# MystiqueJamma.net
KiCad netlist of a schematic drawn in EAGLE
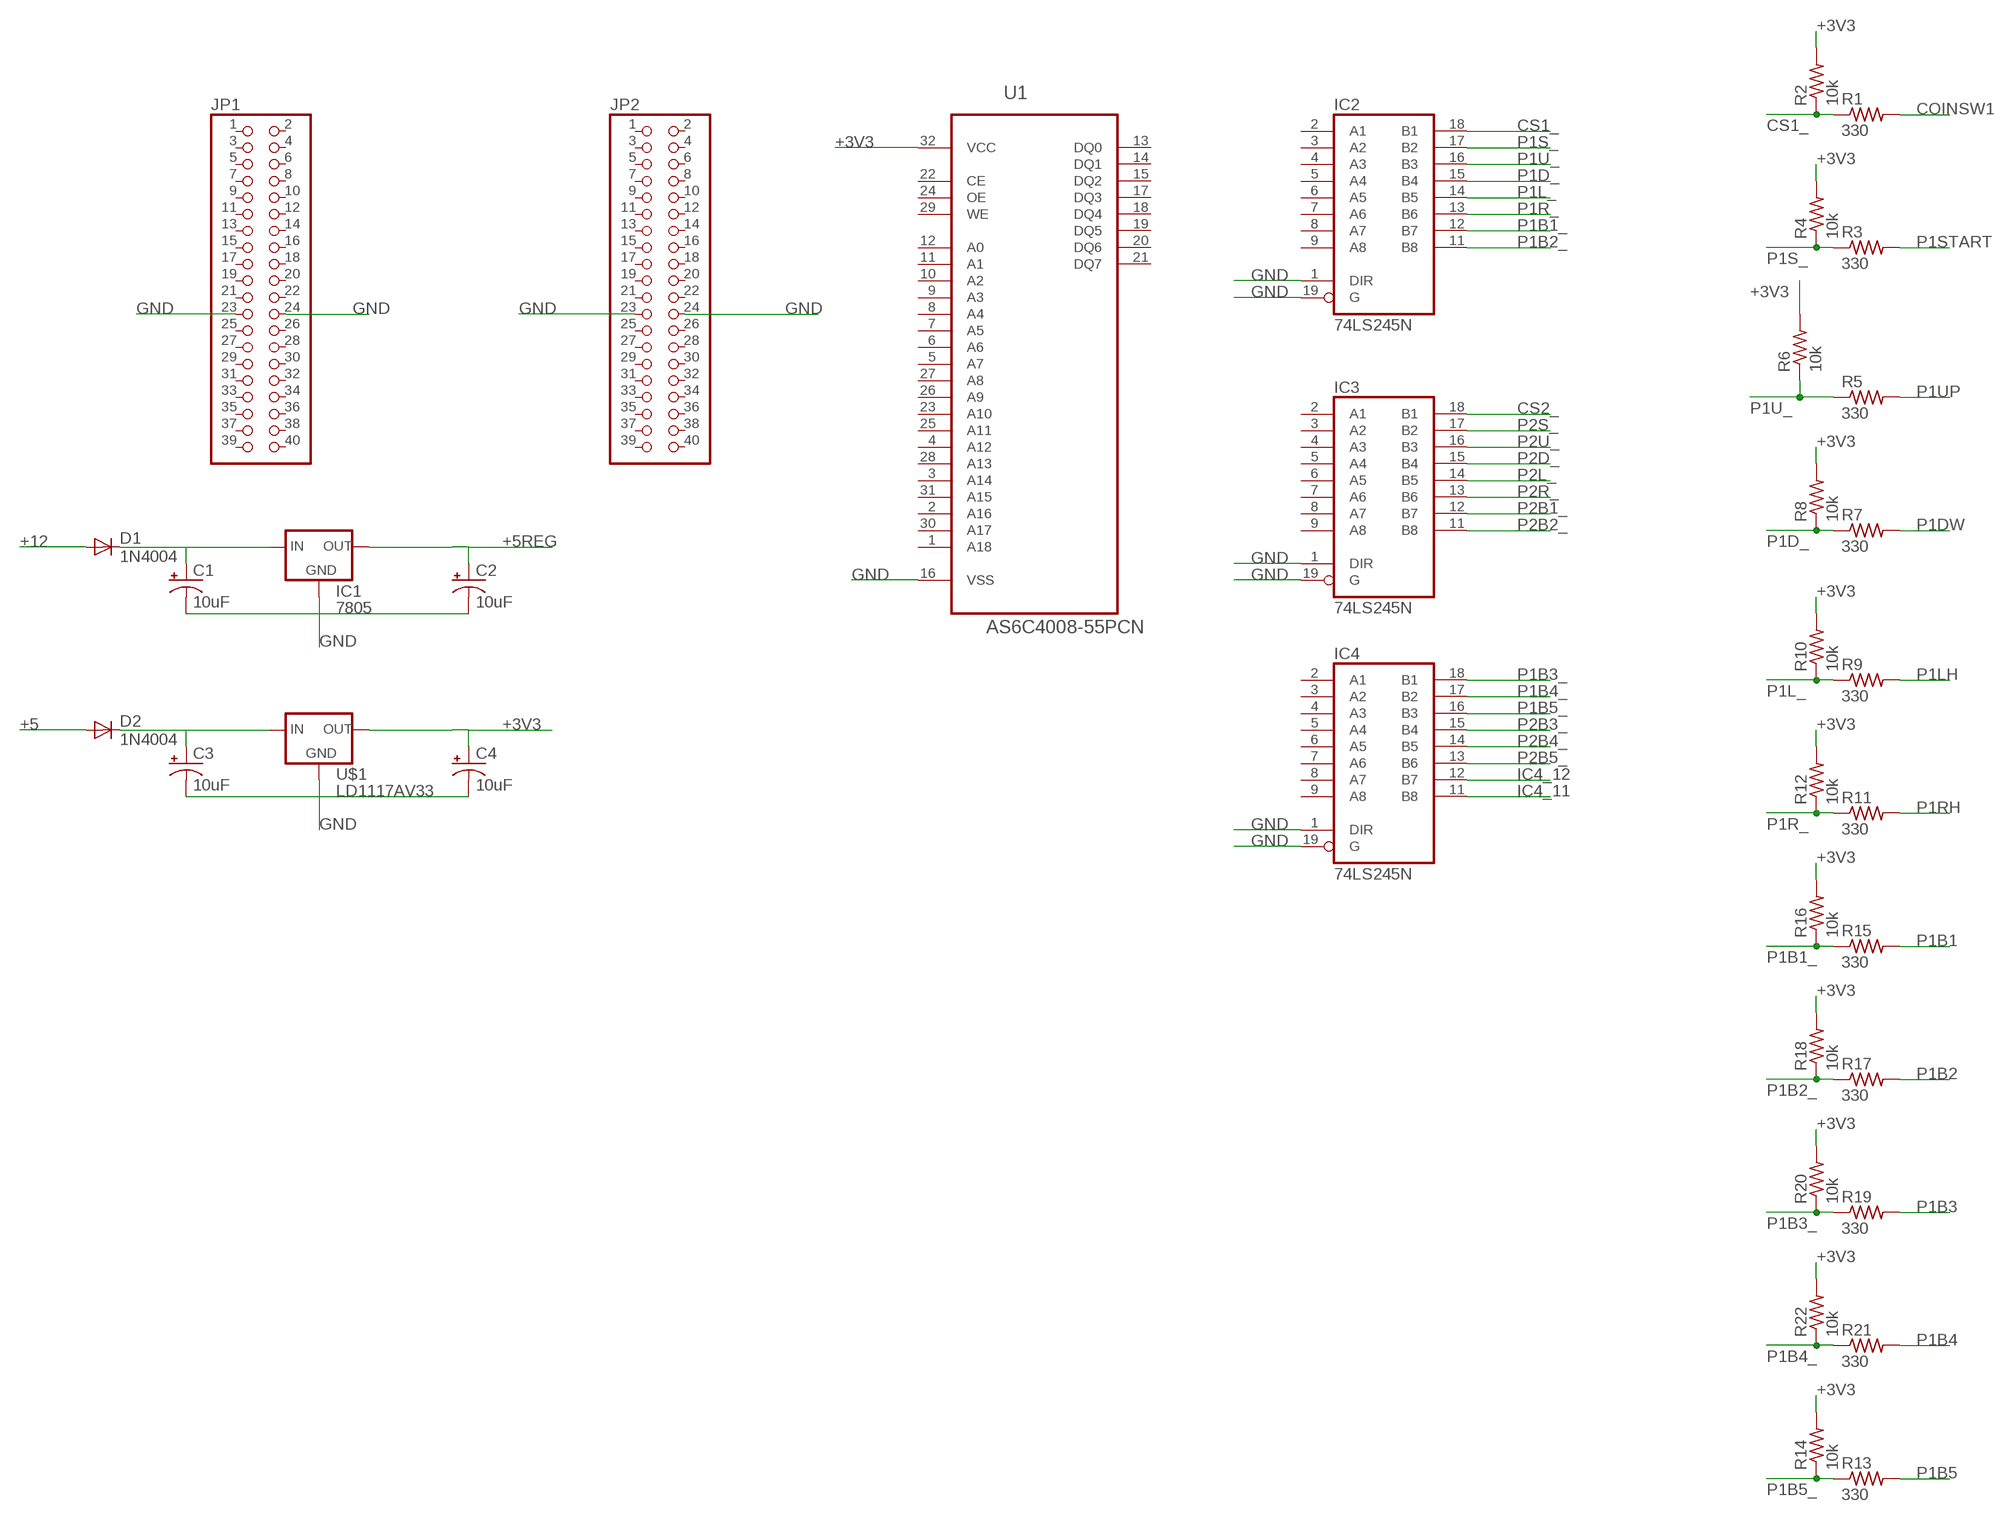
[diagram p0: schematic, sheet 1]

(export (version "E")
  (design (tool "Eeschema 10.0.6"))
  (components
    (comp (ref "C1")
      (value "10uF")
      (footprint "eagle-import:E2,5-5")
      (libsource (lib "eagle-import") (part "CPOL-USE2.5-5"))
    )
    (comp (ref "C2")
      (value "10uF")
      (footprint "eagle-import:E2,5-5")
      (libsource (lib "eagle-import") (part "CPOL-USE2.5-5"))
    )
    (comp (ref "C3")
      (value "10uF")
      (footprint "eagle-import:E2,5-5")
      (libsource (lib "eagle-import") (part "CPOL-USE2.5-5"))
    )
    (comp (ref "C4")
      (value "10uF")
      (footprint "eagle-import:E2,5-5")
      (libsource (lib "eagle-import") (part "CPOL-USE2.5-5"))
    )
    (comp (ref "D1")
      (value "1N4004")
      (footprint "eagle-import:DO41-10")
      (libsource (lib "eagle-import") (part "1N4004"))
    )
    (comp (ref "D2")
      (value "1N4004")
      (footprint "eagle-import:DO41-10")
      (libsource (lib "eagle-import") (part "1N4004"))
    )
    (comp (ref "IC1")
      (value "7805")
      (footprint "eagle-import:TO220-IGO")
      (libsource (lib "eagle-import") (part "V_REG_78XXSINK"))
    )
    (comp (ref "IC2")
      (value "74LS245N")
      (footprint "eagle-import:DIL20")
      (libsource (lib "eagle-import") (part "74245NLS"))
    )
    (comp (ref "IC3")
      (value "74LS245N")
      (footprint "eagle-import:DIL20")
      (libsource (lib "eagle-import") (part "74245NLS"))
    )
    (comp (ref "IC4")
      (value "74LS245N")
      (footprint "eagle-import:DIL20")
      (libsource (lib "eagle-import") (part "74245NLS"))
    )
    (comp (ref "JP1")
      (value "PINHD-2X20")
      (footprint "eagle-import:2X20")
      (libsource (lib "eagle-import") (part "PINHD-2X20"))
    )
    (comp (ref "JP2")
      (value "PINHD-2X20")
      (footprint "eagle-import:2X20")
      (libsource (lib "eagle-import") (part "PINHD-2X20"))
    )
    (comp (ref "R1")
      (value "330")
      (footprint "eagle-import:0207_7")
      (libsource (lib "eagle-import") (part "R-US_0207/7"))
    )
    (comp (ref "R2")
      (value "10k")
      (footprint "eagle-import:0207_7")
      (libsource (lib "eagle-import") (part "R-US_0207/7"))
    )
    (comp (ref "R3")
      (value "330")
      (footprint "eagle-import:0207_7")
      (libsource (lib "eagle-import") (part "R-US_0207/7"))
    )
    (comp (ref "R4")
      (value "10k")
      (footprint "eagle-import:0207_7")
      (libsource (lib "eagle-import") (part "R-US_0207/7"))
    )
    (comp (ref "R5")
      (value "330")
      (footprint "eagle-import:0207_7")
      (libsource (lib "eagle-import") (part "R-US_0207/7"))
    )
    (comp (ref "R6")
      (value "10k")
      (footprint "eagle-import:0207_7")
      (libsource (lib "eagle-import") (part "R-US_0207/7"))
    )
    (comp (ref "R7")
      (value "330")
      (footprint "eagle-import:0207_7")
      (libsource (lib "eagle-import") (part "R-US_0207/7"))
    )
    (comp (ref "R8")
      (value "10k")
      (footprint "eagle-import:0207_7")
      (libsource (lib "eagle-import") (part "R-US_0207/7"))
    )
    (comp (ref "R9")
      (value "330")
      (footprint "eagle-import:0207_7")
      (libsource (lib "eagle-import") (part "R-US_0207/7"))
    )
    (comp (ref "R10")
      (value "10k")
      (footprint "eagle-import:0207_7")
      (libsource (lib "eagle-import") (part "R-US_0207/7"))
    )
    (comp (ref "R11")
      (value "330")
      (footprint "eagle-import:0207_7")
      (libsource (lib "eagle-import") (part "R-US_0207/7"))
    )
    (comp (ref "R12")
      (value "10k")
      (footprint "eagle-import:0207_7")
      (libsource (lib "eagle-import") (part "R-US_0207/7"))
    )
    (comp (ref "R13")
      (value "330")
      (footprint "eagle-import:0207_7")
      (libsource (lib "eagle-import") (part "R-US_0207/7"))
    )
    (comp (ref "R14")
      (value "10k")
      (footprint "eagle-import:0207_7")
      (libsource (lib "eagle-import") (part "R-US_0207/7"))
    )
    (comp (ref "R15")
      (value "330")
      (footprint "eagle-import:0207_7")
      (libsource (lib "eagle-import") (part "R-US_0207/7"))
    )
    (comp (ref "R16")
      (value "10k")
      (footprint "eagle-import:0207_7")
      (libsource (lib "eagle-import") (part "R-US_0207/7"))
    )
    (comp (ref "R17")
      (value "330")
      (footprint "eagle-import:0207_7")
      (libsource (lib "eagle-import") (part "R-US_0207/7"))
    )
    (comp (ref "R18")
      (value "10k")
      (footprint "eagle-import:0207_7")
      (libsource (lib "eagle-import") (part "R-US_0207/7"))
    )
    (comp (ref "R19")
      (value "330")
      (footprint "eagle-import:0207_7")
      (libsource (lib "eagle-import") (part "R-US_0207/7"))
    )
    (comp (ref "R20")
      (value "10k")
      (footprint "eagle-import:0207_7")
      (libsource (lib "eagle-import") (part "R-US_0207/7"))
    )
    (comp (ref "R21")
      (value "330")
      (footprint "eagle-import:0207_7")
      (libsource (lib "eagle-import") (part "R-US_0207/7"))
    )
    (comp (ref "R22")
      (value "10k")
      (footprint "eagle-import:0207_7")
      (libsource (lib "eagle-import") (part "R-US_0207/7"))
    )
    (comp (ref "U$1")
      (value "LD1117AV33")
      (footprint "eagle-import:TO220-IGO")
      (libsource (lib "eagle-import") (part "SparkFun-IC-Power_526_V_REG_78XXSINK"))
    )
    (comp (ref "U1")
      (value "AS6C4008-55PCN")
      (footprint "eagle-import:DIP254P1524X393-32")
      (libsource (lib "eagle-import") (part "AS6C4008-55PCN"))
    )
  )
  (nets
    (net (code "1") (name "/+3V3") (class "Default")
      (node (ref "C4") (pin "+") (pinfunction "+_+") (pintype "passive"))
      (node (ref "R10") (pin "2") (pinfunction "2_2") (pintype "passive"))
      (node (ref "R12") (pin "2") (pinfunction "2_2") (pintype "passive"))
      (node (ref "R14") (pin "2") (pinfunction "2_2") (pintype "passive"))
      (node (ref "R16") (pin "2") (pinfunction "2_2") (pintype "passive"))
      (node (ref "R18") (pin "2") (pinfunction "2_2") (pintype "passive"))
      (node (ref "R2") (pin "2") (pinfunction "2_2") (pintype "passive"))
      (node (ref "R20") (pin "2") (pinfunction "2_2") (pintype "passive"))
      (node (ref "R22") (pin "2") (pinfunction "2_2") (pintype "passive"))
      (node (ref "R4") (pin "2") (pinfunction "2_2") (pintype "passive"))
      (node (ref "R6") (pin "2") (pinfunction "2_2") (pintype "passive"))
      (node (ref "R8") (pin "2") (pinfunction "2_2") (pintype "passive"))
      (node (ref "U$1") (pin "OUT") (pinfunction "OUT_OUT") (pintype "passive"))
      (node (ref "U1") (pin "32") (pinfunction "VCC_32") (pintype "power_in"))
    )
    (net (code "2") (name "/+5") (class "Default")
      (node (ref "D2") (pin "A") (pinfunction "A_A") (pintype "passive"))
    )
    (net (code "3") (name "/+5REG") (class "Default")
      (node (ref "C2") (pin "+") (pinfunction "+_+") (pintype "passive"))
      (node (ref "IC1") (pin "OUT") (pinfunction "OUT_OUT") (pintype "output"))
    )
    (net (code "4") (name "/+12") (class "Default")
      (node (ref "D1") (pin "A") (pinfunction "A_A") (pintype "passive"))
    )
    (net (code "5") (name "/COINSW1") (class "Default")
      (node (ref "R1") (pin "2") (pinfunction "2_2") (pintype "passive"))
    )
    (net (code "6") (name "/CS1_") (class "Default")
      (node (ref "IC2") (pin "18") (pinfunction "B1_18") (pintype "bidirectional"))
      (node (ref "R1") (pin "1") (pinfunction "1_1") (pintype "passive"))
      (node (ref "R2") (pin "1") (pinfunction "1_1") (pintype "passive"))
    )
    (net (code "7") (name "/CS2_") (class "Default")
      (node (ref "IC3") (pin "18") (pinfunction "B1_18") (pintype "bidirectional"))
    )
    (net (code "8") (name "/GND") (class "Default")
      (node (ref "C1") (pin "-") (pinfunction "-_-") (pintype "passive"))
      (node (ref "C2") (pin "-") (pinfunction "-_-") (pintype "passive"))
      (node (ref "C3") (pin "-") (pinfunction "-_-") (pintype "passive"))
      (node (ref "C4") (pin "-") (pinfunction "-_-") (pintype "passive"))
      (node (ref "IC1") (pin "GND") (pinfunction "GND_GND") (pintype "input"))
      (node (ref "IC2") (pin "1") (pinfunction "DIR_1") (pintype "input"))
      (node (ref "IC2") (pin "19") (pinfunction "G_19") (pintype "input"))
      (node (ref "IC3") (pin "1") (pinfunction "DIR_1") (pintype "input"))
      (node (ref "IC3") (pin "19") (pinfunction "G_19") (pintype "input"))
      (node (ref "IC4") (pin "1") (pinfunction "DIR_1") (pintype "input"))
      (node (ref "IC4") (pin "19") (pinfunction "G_19") (pintype "input"))
      (node (ref "JP1") (pin "23") (pinfunction "23_23") (pintype "passive"))
      (node (ref "JP1") (pin "24") (pinfunction "24_24") (pintype "passive"))
      (node (ref "JP2") (pin "23") (pinfunction "23_23") (pintype "passive"))
      (node (ref "JP2") (pin "24") (pinfunction "24_24") (pintype "passive"))
      (node (ref "U$1") (pin "GND") (pinfunction "GND_GND") (pintype "input"))
      (node (ref "U1") (pin "16") (pinfunction "VSS_16") (pintype "bidirectional"))
    )
    (net (code "9") (name "/IC4_11") (class "Default")
      (node (ref "IC4") (pin "11") (pinfunction "B8_11") (pintype "bidirectional"))
    )
    (net (code "10") (name "/IC4_12") (class "Default")
      (node (ref "IC4") (pin "12") (pinfunction "B7_12") (pintype "bidirectional"))
    )
    (net (code "11") (name "/P1B1") (class "Default")
      (node (ref "R15") (pin "2") (pinfunction "2_2") (pintype "passive"))
    )
    (net (code "12") (name "/P1B1_") (class "Default")
      (node (ref "IC2") (pin "12") (pinfunction "B7_12") (pintype "bidirectional"))
      (node (ref "R15") (pin "1") (pinfunction "1_1") (pintype "passive"))
      (node (ref "R16") (pin "1") (pinfunction "1_1") (pintype "passive"))
    )
    (net (code "13") (name "/P1B2") (class "Default")
      (node (ref "R17") (pin "2") (pinfunction "2_2") (pintype "passive"))
    )
    (net (code "14") (name "/P1B2_") (class "Default")
      (node (ref "IC2") (pin "11") (pinfunction "B8_11") (pintype "bidirectional"))
      (node (ref "R17") (pin "1") (pinfunction "1_1") (pintype "passive"))
      (node (ref "R18") (pin "1") (pinfunction "1_1") (pintype "passive"))
    )
    (net (code "15") (name "/P1B3") (class "Default")
      (node (ref "R19") (pin "2") (pinfunction "2_2") (pintype "passive"))
    )
    (net (code "16") (name "/P1B3_") (class "Default")
      (node (ref "IC4") (pin "18") (pinfunction "B1_18") (pintype "bidirectional"))
      (node (ref "R19") (pin "1") (pinfunction "1_1") (pintype "passive"))
      (node (ref "R20") (pin "1") (pinfunction "1_1") (pintype "passive"))
    )
    (net (code "17") (name "/P1B4") (class "Default")
      (node (ref "R21") (pin "2") (pinfunction "2_2") (pintype "passive"))
    )
    (net (code "18") (name "/P1B4_") (class "Default")
      (node (ref "IC4") (pin "17") (pinfunction "B2_17") (pintype "bidirectional"))
      (node (ref "R21") (pin "1") (pinfunction "1_1") (pintype "passive"))
      (node (ref "R22") (pin "1") (pinfunction "1_1") (pintype "passive"))
    )
    (net (code "19") (name "/P1B5") (class "Default")
      (node (ref "R13") (pin "2") (pinfunction "2_2") (pintype "passive"))
    )
    (net (code "20") (name "/P1B5_") (class "Default")
      (node (ref "IC4") (pin "16") (pinfunction "B3_16") (pintype "bidirectional"))
      (node (ref "R13") (pin "1") (pinfunction "1_1") (pintype "passive"))
      (node (ref "R14") (pin "1") (pinfunction "1_1") (pintype "passive"))
    )
    (net (code "21") (name "/P1DW") (class "Default")
      (node (ref "R7") (pin "2") (pinfunction "2_2") (pintype "passive"))
    )
    (net (code "22") (name "/P1D_") (class "Default")
      (node (ref "IC2") (pin "15") (pinfunction "B4_15") (pintype "bidirectional"))
      (node (ref "R7") (pin "1") (pinfunction "1_1") (pintype "passive"))
      (node (ref "R8") (pin "1") (pinfunction "1_1") (pintype "passive"))
    )
    (net (code "23") (name "/P1LH") (class "Default")
      (node (ref "R9") (pin "2") (pinfunction "2_2") (pintype "passive"))
    )
    (net (code "24") (name "/P1L_") (class "Default")
      (node (ref "IC2") (pin "14") (pinfunction "B5_14") (pintype "bidirectional"))
      (node (ref "R10") (pin "1") (pinfunction "1_1") (pintype "passive"))
      (node (ref "R9") (pin "1") (pinfunction "1_1") (pintype "passive"))
    )
    (net (code "25") (name "/P1RH") (class "Default")
      (node (ref "R11") (pin "2") (pinfunction "2_2") (pintype "passive"))
    )
    (net (code "26") (name "/P1R_") (class "Default")
      (node (ref "IC2") (pin "13") (pinfunction "B6_13") (pintype "bidirectional"))
      (node (ref "R11") (pin "1") (pinfunction "1_1") (pintype "passive"))
      (node (ref "R12") (pin "1") (pinfunction "1_1") (pintype "passive"))
    )
    (net (code "27") (name "/P1START") (class "Default")
      (node (ref "R3") (pin "2") (pinfunction "2_2") (pintype "passive"))
    )
    (net (code "28") (name "/P1S_") (class "Default")
      (node (ref "IC2") (pin "17") (pinfunction "B2_17") (pintype "bidirectional"))
      (node (ref "R3") (pin "1") (pinfunction "1_1") (pintype "passive"))
      (node (ref "R4") (pin "1") (pinfunction "1_1") (pintype "passive"))
    )
    (net (code "29") (name "/P1UP") (class "Default")
      (node (ref "R5") (pin "2") (pinfunction "2_2") (pintype "passive"))
    )
    (net (code "30") (name "/P1U_") (class "Default")
      (node (ref "IC2") (pin "16") (pinfunction "B3_16") (pintype "bidirectional"))
      (node (ref "R5") (pin "1") (pinfunction "1_1") (pintype "passive"))
      (node (ref "R6") (pin "1") (pinfunction "1_1") (pintype "passive"))
    )
    (net (code "31") (name "/P2B1_") (class "Default")
      (node (ref "IC3") (pin "12") (pinfunction "B7_12") (pintype "bidirectional"))
    )
    (net (code "32") (name "/P2B2_") (class "Default")
      (node (ref "IC3") (pin "11") (pinfunction "B8_11") (pintype "bidirectional"))
    )
    (net (code "33") (name "/P2B3_") (class "Default")
      (node (ref "IC4") (pin "15") (pinfunction "B4_15") (pintype "bidirectional"))
    )
    (net (code "34") (name "/P2B4_") (class "Default")
      (node (ref "IC4") (pin "14") (pinfunction "B5_14") (pintype "bidirectional"))
    )
    (net (code "35") (name "/P2B5_") (class "Default")
      (node (ref "IC4") (pin "13") (pinfunction "B6_13") (pintype "bidirectional"))
    )
    (net (code "36") (name "/P2D_") (class "Default")
      (node (ref "IC3") (pin "15") (pinfunction "B4_15") (pintype "bidirectional"))
    )
    (net (code "37") (name "/P2L_") (class "Default")
      (node (ref "IC3") (pin "14") (pinfunction "B5_14") (pintype "bidirectional"))
    )
    (net (code "38") (name "/P2R_") (class "Default")
      (node (ref "IC3") (pin "13") (pinfunction "B6_13") (pintype "bidirectional"))
    )
    (net (code "39") (name "/P2S_") (class "Default")
      (node (ref "IC3") (pin "17") (pinfunction "B2_17") (pintype "bidirectional"))
    )
    (net (code "40") (name "/P2U_") (class "Default")
      (node (ref "IC3") (pin "16") (pinfunction "B3_16") (pintype "bidirectional"))
    )
    (net (code "41") (name "Net-(C1-Pad+)") (class "Default")
      (node (ref "C1") (pin "+") (pinfunction "+_+") (pintype "passive"))
      (node (ref "D1") (pin "C") (pinfunction "C_C") (pintype "passive"))
      (node (ref "IC1") (pin "IN") (pinfunction "IN_IN") (pintype "input"))
    )
    (net (code "42") (name "Net-(C3-Pad+)") (class "Default")
      (node (ref "C3") (pin "+") (pinfunction "+_+") (pintype "passive"))
      (node (ref "D2") (pin "C") (pinfunction "C_C") (pintype "passive"))
      (node (ref "U$1") (pin "IN") (pinfunction "IN_IN") (pintype "input"))
    )
    (net (code "43") (name "unconnected-(IC2A-A1-Pad2)") (class "Default")
      (node (ref "IC2") (pin "2") (pinfunction "A1_2") (pintype "bidirectional"))
    )
    (net (code "44") (name "unconnected-(IC2A-A2-Pad3)") (class "Default")
      (node (ref "IC2") (pin "3") (pinfunction "A2_3") (pintype "bidirectional"))
    )
    (net (code "45") (name "unconnected-(IC2A-A3-Pad4)") (class "Default")
      (node (ref "IC2") (pin "4") (pinfunction "A3_4") (pintype "bidirectional"))
    )
    (net (code "46") (name "unconnected-(IC2A-A4-Pad5)") (class "Default")
      (node (ref "IC2") (pin "5") (pinfunction "A4_5") (pintype "bidirectional"))
    )
    (net (code "47") (name "unconnected-(IC2A-A5-Pad6)") (class "Default")
      (node (ref "IC2") (pin "6") (pinfunction "A5_6") (pintype "bidirectional"))
    )
    (net (code "48") (name "unconnected-(IC2A-A6-Pad7)") (class "Default")
      (node (ref "IC2") (pin "7") (pinfunction "A6_7") (pintype "bidirectional"))
    )
    (net (code "49") (name "unconnected-(IC2A-A7-Pad8)") (class "Default")
      (node (ref "IC2") (pin "8") (pinfunction "A7_8") (pintype "bidirectional"))
    )
    (net (code "50") (name "unconnected-(IC2A-A8-Pad9)") (class "Default")
      (node (ref "IC2") (pin "9") (pinfunction "A8_9") (pintype "bidirectional"))
    )
    (net (code "51") (name "unconnected-(IC3A-A1-Pad2)") (class "Default")
      (node (ref "IC3") (pin "2") (pinfunction "A1_2") (pintype "bidirectional"))
    )
    (net (code "52") (name "unconnected-(IC3A-A2-Pad3)") (class "Default")
      (node (ref "IC3") (pin "3") (pinfunction "A2_3") (pintype "bidirectional"))
    )
    (net (code "53") (name "unconnected-(IC3A-A3-Pad4)") (class "Default")
      (node (ref "IC3") (pin "4") (pinfunction "A3_4") (pintype "bidirectional"))
    )
    (net (code "54") (name "unconnected-(IC3A-A4-Pad5)") (class "Default")
      (node (ref "IC3") (pin "5") (pinfunction "A4_5") (pintype "bidirectional"))
    )
    (net (code "55") (name "unconnected-(IC3A-A5-Pad6)") (class "Default")
      (node (ref "IC3") (pin "6") (pinfunction "A5_6") (pintype "bidirectional"))
    )
    (net (code "56") (name "unconnected-(IC3A-A6-Pad7)") (class "Default")
      (node (ref "IC3") (pin "7") (pinfunction "A6_7") (pintype "bidirectional"))
    )
    (net (code "57") (name "unconnected-(IC3A-A7-Pad8)") (class "Default")
      (node (ref "IC3") (pin "8") (pinfunction "A7_8") (pintype "bidirectional"))
    )
    (net (code "58") (name "unconnected-(IC3A-A8-Pad9)") (class "Default")
      (node (ref "IC3") (pin "9") (pinfunction "A8_9") (pintype "bidirectional"))
    )
    (net (code "59") (name "unconnected-(IC4A-A1-Pad2)") (class "Default")
      (node (ref "IC4") (pin "2") (pinfunction "A1_2") (pintype "bidirectional"))
    )
    (net (code "60") (name "unconnected-(IC4A-A2-Pad3)") (class "Default")
      (node (ref "IC4") (pin "3") (pinfunction "A2_3") (pintype "bidirectional"))
    )
    (net (code "61") (name "unconnected-(IC4A-A3-Pad4)") (class "Default")
      (node (ref "IC4") (pin "4") (pinfunction "A3_4") (pintype "bidirectional"))
    )
    (net (code "62") (name "unconnected-(IC4A-A4-Pad5)") (class "Default")
      (node (ref "IC4") (pin "5") (pinfunction "A4_5") (pintype "bidirectional"))
    )
    (net (code "63") (name "unconnected-(IC4A-A5-Pad6)") (class "Default")
      (node (ref "IC4") (pin "6") (pinfunction "A5_6") (pintype "bidirectional"))
    )
    (net (code "64") (name "unconnected-(IC4A-A6-Pad7)") (class "Default")
      (node (ref "IC4") (pin "7") (pinfunction "A6_7") (pintype "bidirectional"))
    )
    (net (code "65") (name "unconnected-(IC4A-A7-Pad8)") (class "Default")
      (node (ref "IC4") (pin "8") (pinfunction "A7_8") (pintype "bidirectional"))
    )
    (net (code "66") (name "unconnected-(IC4A-A8-Pad9)") (class "Default")
      (node (ref "IC4") (pin "9") (pinfunction "A8_9") (pintype "bidirectional"))
    )
    (net (code "67") (name "unconnected-(JP1-Pad1)") (class "Default")
      (node (ref "JP1") (pin "1") (pinfunction "1_1") (pintype "passive"))
    )
    (net (code "68") (name "unconnected-(JP1-Pad2)") (class "Default")
      (node (ref "JP1") (pin "2") (pinfunction "2_2") (pintype "passive"))
    )
    (net (code "69") (name "unconnected-(JP1-Pad3)") (class "Default")
      (node (ref "JP1") (pin "3") (pinfunction "3_3") (pintype "passive"))
    )
    (net (code "70") (name "unconnected-(JP1-Pad4)") (class "Default")
      (node (ref "JP1") (pin "4") (pinfunction "4_4") (pintype "passive"))
    )
    (net (code "71") (name "unconnected-(JP1-Pad5)") (class "Default")
      (node (ref "JP1") (pin "5") (pinfunction "5_5") (pintype "passive"))
    )
    (net (code "72") (name "unconnected-(JP1-Pad6)") (class "Default")
      (node (ref "JP1") (pin "6") (pinfunction "6_6") (pintype "passive"))
    )
    (net (code "73") (name "unconnected-(JP1-Pad7)") (class "Default")
      (node (ref "JP1") (pin "7") (pinfunction "7_7") (pintype "passive"))
    )
    (net (code "74") (name "unconnected-(JP1-Pad8)") (class "Default")
      (node (ref "JP1") (pin "8") (pinfunction "8_8") (pintype "passive"))
    )
    (net (code "75") (name "unconnected-(JP1-Pad9)") (class "Default")
      (node (ref "JP1") (pin "9") (pinfunction "9_9") (pintype "passive"))
    )
    (net (code "76") (name "unconnected-(JP1-Pad10)") (class "Default")
      (node (ref "JP1") (pin "10") (pinfunction "10_10") (pintype "passive"))
    )
    (net (code "77") (name "unconnected-(JP1-Pad11)") (class "Default")
      (node (ref "JP1") (pin "11") (pinfunction "11_11") (pintype "passive"))
    )
    (net (code "78") (name "unconnected-(JP1-Pad12)") (class "Default")
      (node (ref "JP1") (pin "12") (pinfunction "12_12") (pintype "passive"))
    )
    (net (code "79") (name "unconnected-(JP1-Pad13)") (class "Default")
      (node (ref "JP1") (pin "13") (pinfunction "13_13") (pintype "passive"))
    )
    (net (code "80") (name "unconnected-(JP1-Pad14)") (class "Default")
      (node (ref "JP1") (pin "14") (pinfunction "14_14") (pintype "passive"))
    )
    (net (code "81") (name "unconnected-(JP1-Pad15)") (class "Default")
      (node (ref "JP1") (pin "15") (pinfunction "15_15") (pintype "passive"))
    )
    (net (code "82") (name "unconnected-(JP1-Pad16)") (class "Default")
      (node (ref "JP1") (pin "16") (pinfunction "16_16") (pintype "passive"))
    )
    (net (code "83") (name "unconnected-(JP1-Pad17)") (class "Default")
      (node (ref "JP1") (pin "17") (pinfunction "17_17") (pintype "passive"))
    )
    (net (code "84") (name "unconnected-(JP1-Pad18)") (class "Default")
      (node (ref "JP1") (pin "18") (pinfunction "18_18") (pintype "passive"))
    )
    (net (code "85") (name "unconnected-(JP1-Pad19)") (class "Default")
      (node (ref "JP1") (pin "19") (pinfunction "19_19") (pintype "passive"))
    )
    (net (code "86") (name "unconnected-(JP1-Pad20)") (class "Default")
      (node (ref "JP1") (pin "20") (pinfunction "20_20") (pintype "passive"))
    )
    (net (code "87") (name "unconnected-(JP1-Pad21)") (class "Default")
      (node (ref "JP1") (pin "21") (pinfunction "21_21") (pintype "passive"))
    )
    (net (code "88") (name "unconnected-(JP1-Pad22)") (class "Default")
      (node (ref "JP1") (pin "22") (pinfunction "22_22") (pintype "passive"))
    )
    (net (code "89") (name "unconnected-(JP1-Pad25)") (class "Default")
      (node (ref "JP1") (pin "25") (pinfunction "25_25") (pintype "passive"))
    )
    (net (code "90") (name "unconnected-(JP1-Pad26)") (class "Default")
      (node (ref "JP1") (pin "26") (pinfunction "26_26") (pintype "passive"))
    )
    (net (code "91") (name "unconnected-(JP1-Pad27)") (class "Default")
      (node (ref "JP1") (pin "27") (pinfunction "27_27") (pintype "passive"))
    )
    (net (code "92") (name "unconnected-(JP1-Pad28)") (class "Default")
      (node (ref "JP1") (pin "28") (pinfunction "28_28") (pintype "passive"))
    )
    (net (code "93") (name "unconnected-(JP1-Pad29)") (class "Default")
      (node (ref "JP1") (pin "29") (pinfunction "29_29") (pintype "passive"))
    )
    (net (code "94") (name "unconnected-(JP1-Pad30)") (class "Default")
      (node (ref "JP1") (pin "30") (pinfunction "30_30") (pintype "passive"))
    )
    (net (code "95") (name "unconnected-(JP1-Pad31)") (class "Default")
      (node (ref "JP1") (pin "31") (pinfunction "31_31") (pintype "passive"))
    )
    (net (code "96") (name "unconnected-(JP1-Pad32)") (class "Default")
      (node (ref "JP1") (pin "32") (pinfunction "32_32") (pintype "passive"))
    )
    (net (code "97") (name "unconnected-(JP1-Pad33)") (class "Default")
      (node (ref "JP1") (pin "33") (pinfunction "33_33") (pintype "passive"))
    )
    (net (code "98") (name "unconnected-(JP1-Pad34)") (class "Default")
      (node (ref "JP1") (pin "34") (pinfunction "34_34") (pintype "passive"))
    )
    (net (code "99") (name "unconnected-(JP1-Pad35)") (class "Default")
      (node (ref "JP1") (pin "35") (pinfunction "35_35") (pintype "passive"))
    )
    (net (code "100") (name "unconnected-(JP1-Pad36)") (class "Default")
      (node (ref "JP1") (pin "36") (pinfunction "36_36") (pintype "passive"))
    )
    (net (code "101") (name "unconnected-(JP1-Pad37)") (class "Default")
      (node (ref "JP1") (pin "37") (pinfunction "37_37") (pintype "passive"))
    )
    (net (code "102") (name "unconnected-(JP1-Pad38)") (class "Default")
      (node (ref "JP1") (pin "38") (pinfunction "38_38") (pintype "passive"))
    )
    (net (code "103") (name "unconnected-(JP1-Pad39)") (class "Default")
      (node (ref "JP1") (pin "39") (pinfunction "39_39") (pintype "passive"))
    )
    (net (code "104") (name "unconnected-(JP1-Pad40)") (class "Default")
      (node (ref "JP1") (pin "40") (pinfunction "40_40") (pintype "passive"))
    )
    (net (code "105") (name "unconnected-(JP2-Pad1)") (class "Default")
      (node (ref "JP2") (pin "1") (pinfunction "1_1") (pintype "passive"))
    )
    (net (code "106") (name "unconnected-(JP2-Pad2)") (class "Default")
      (node (ref "JP2") (pin "2") (pinfunction "2_2") (pintype "passive"))
    )
    (net (code "107") (name "unconnected-(JP2-Pad3)") (class "Default")
      (node (ref "JP2") (pin "3") (pinfunction "3_3") (pintype "passive"))
    )
    (net (code "108") (name "unconnected-(JP2-Pad4)") (class "Default")
      (node (ref "JP2") (pin "4") (pinfunction "4_4") (pintype "passive"))
    )
    (net (code "109") (name "unconnected-(JP2-Pad5)") (class "Default")
      (node (ref "JP2") (pin "5") (pinfunction "5_5") (pintype "passive"))
    )
    (net (code "110") (name "unconnected-(JP2-Pad6)") (class "Default")
      (node (ref "JP2") (pin "6") (pinfunction "6_6") (pintype "passive"))
    )
    (net (code "111") (name "unconnected-(JP2-Pad7)") (class "Default")
      (node (ref "JP2") (pin "7") (pinfunction "7_7") (pintype "passive"))
    )
    (net (code "112") (name "unconnected-(JP2-Pad8)") (class "Default")
      (node (ref "JP2") (pin "8") (pinfunction "8_8") (pintype "passive"))
    )
    (net (code "113") (name "unconnected-(JP2-Pad9)") (class "Default")
      (node (ref "JP2") (pin "9") (pinfunction "9_9") (pintype "passive"))
    )
    (net (code "114") (name "unconnected-(JP2-Pad10)") (class "Default")
      (node (ref "JP2") (pin "10") (pinfunction "10_10") (pintype "passive"))
    )
    (net (code "115") (name "unconnected-(JP2-Pad11)") (class "Default")
      (node (ref "JP2") (pin "11") (pinfunction "11_11") (pintype "passive"))
    )
    (net (code "116") (name "unconnected-(JP2-Pad12)") (class "Default")
      (node (ref "JP2") (pin "12") (pinfunction "12_12") (pintype "passive"))
    )
    (net (code "117") (name "unconnected-(JP2-Pad13)") (class "Default")
      (node (ref "JP2") (pin "13") (pinfunction "13_13") (pintype "passive"))
    )
    (net (code "118") (name "unconnected-(JP2-Pad14)") (class "Default")
      (node (ref "JP2") (pin "14") (pinfunction "14_14") (pintype "passive"))
    )
    (net (code "119") (name "unconnected-(JP2-Pad15)") (class "Default")
      (node (ref "JP2") (pin "15") (pinfunction "15_15") (pintype "passive"))
    )
    (net (code "120") (name "unconnected-(JP2-Pad16)") (class "Default")
      (node (ref "JP2") (pin "16") (pinfunction "16_16") (pintype "passive"))
    )
    (net (code "121") (name "unconnected-(JP2-Pad17)") (class "Default")
      (node (ref "JP2") (pin "17") (pinfunction "17_17") (pintype "passive"))
    )
    (net (code "122") (name "unconnected-(JP2-Pad18)") (class "Default")
      (node (ref "JP2") (pin "18") (pinfunction "18_18") (pintype "passive"))
    )
    (net (code "123") (name "unconnected-(JP2-Pad19)") (class "Default")
      (node (ref "JP2") (pin "19") (pinfunction "19_19") (pintype "passive"))
    )
    (net (code "124") (name "unconnected-(JP2-Pad20)") (class "Default")
      (node (ref "JP2") (pin "20") (pinfunction "20_20") (pintype "passive"))
    )
    (net (code "125") (name "unconnected-(JP2-Pad21)") (class "Default")
      (node (ref "JP2") (pin "21") (pinfunction "21_21") (pintype "passive"))
    )
    (net (code "126") (name "unconnected-(JP2-Pad22)") (class "Default")
      (node (ref "JP2") (pin "22") (pinfunction "22_22") (pintype "passive"))
    )
    (net (code "127") (name "unconnected-(JP2-Pad25)") (class "Default")
      (node (ref "JP2") (pin "25") (pinfunction "25_25") (pintype "passive"))
    )
    (net (code "128") (name "unconnected-(JP2-Pad26)") (class "Default")
      (node (ref "JP2") (pin "26") (pinfunction "26_26") (pintype "passive"))
    )
    (net (code "129") (name "unconnected-(JP2-Pad27)") (class "Default")
      (node (ref "JP2") (pin "27") (pinfunction "27_27") (pintype "passive"))
    )
    (net (code "130") (name "unconnected-(JP2-Pad28)") (class "Default")
      (node (ref "JP2") (pin "28") (pinfunction "28_28") (pintype "passive"))
    )
    (net (code "131") (name "unconnected-(JP2-Pad29)") (class "Default")
      (node (ref "JP2") (pin "29") (pinfunction "29_29") (pintype "passive"))
    )
    (net (code "132") (name "unconnected-(JP2-Pad30)") (class "Default")
      (node (ref "JP2") (pin "30") (pinfunction "30_30") (pintype "passive"))
    )
    (net (code "133") (name "unconnected-(JP2-Pad31)") (class "Default")
      (node (ref "JP2") (pin "31") (pinfunction "31_31") (pintype "passive"))
    )
    (net (code "134") (name "unconnected-(JP2-Pad32)") (class "Default")
      (node (ref "JP2") (pin "32") (pinfunction "32_32") (pintype "passive"))
    )
    (net (code "135") (name "unconnected-(JP2-Pad33)") (class "Default")
      (node (ref "JP2") (pin "33") (pinfunction "33_33") (pintype "passive"))
    )
    (net (code "136") (name "unconnected-(JP2-Pad34)") (class "Default")
      (node (ref "JP2") (pin "34") (pinfunction "34_34") (pintype "passive"))
    )
    (net (code "137") (name "unconnected-(JP2-Pad35)") (class "Default")
      (node (ref "JP2") (pin "35") (pinfunction "35_35") (pintype "passive"))
    )
    (net (code "138") (name "unconnected-(JP2-Pad36)") (class "Default")
      (node (ref "JP2") (pin "36") (pinfunction "36_36") (pintype "passive"))
    )
    (net (code "139") (name "unconnected-(JP2-Pad37)") (class "Default")
      (node (ref "JP2") (pin "37") (pinfunction "37_37") (pintype "passive"))
    )
    (net (code "140") (name "unconnected-(JP2-Pad38)") (class "Default")
      (node (ref "JP2") (pin "38") (pinfunction "38_38") (pintype "passive"))
    )
    (net (code "141") (name "unconnected-(JP2-Pad39)") (class "Default")
      (node (ref "JP2") (pin "39") (pinfunction "39_39") (pintype "passive"))
    )
    (net (code "142") (name "unconnected-(JP2-Pad40)") (class "Default")
      (node (ref "JP2") (pin "40") (pinfunction "40_40") (pintype "passive"))
    )
    (net (code "143") (name "unconnected-(U1-A0-Pad12)") (class "Default")
      (node (ref "U1") (pin "12") (pinfunction "A0_12") (pintype "input"))
    )
    (net (code "144") (name "unconnected-(U1-A1-Pad11)") (class "Default")
      (node (ref "U1") (pin "11") (pinfunction "A1_11") (pintype "input"))
    )
    (net (code "145") (name "unconnected-(U1-A2-Pad10)") (class "Default")
      (node (ref "U1") (pin "10") (pinfunction "A2_10") (pintype "input"))
    )
    (net (code "146") (name "unconnected-(U1-A3-Pad9)") (class "Default")
      (node (ref "U1") (pin "9") (pinfunction "A3_9") (pintype "input"))
    )
    (net (code "147") (name "unconnected-(U1-A4-Pad8)") (class "Default")
      (node (ref "U1") (pin "8") (pinfunction "A4_8") (pintype "input"))
    )
    (net (code "148") (name "unconnected-(U1-A5-Pad7)") (class "Default")
      (node (ref "U1") (pin "7") (pinfunction "A5_7") (pintype "input"))
    )
    (net (code "149") (name "unconnected-(U1-A6-Pad6)") (class "Default")
      (node (ref "U1") (pin "6") (pinfunction "A6_6") (pintype "input"))
    )
    (net (code "150") (name "unconnected-(U1-A7-Pad5)") (class "Default")
      (node (ref "U1") (pin "5") (pinfunction "A7_5") (pintype "input"))
    )
    (net (code "151") (name "unconnected-(U1-A8-Pad27)") (class "Default")
      (node (ref "U1") (pin "27") (pinfunction "A8_27") (pintype "input"))
    )
    (net (code "152") (name "unconnected-(U1-A9-Pad26)") (class "Default")
      (node (ref "U1") (pin "26") (pinfunction "A9_26") (pintype "input"))
    )
    (net (code "153") (name "unconnected-(U1-A10-Pad23)") (class "Default")
      (node (ref "U1") (pin "23") (pinfunction "A10_23") (pintype "input"))
    )
    (net (code "154") (name "unconnected-(U1-A11-Pad25)") (class "Default")
      (node (ref "U1") (pin "25") (pinfunction "A11_25") (pintype "input"))
    )
    (net (code "155") (name "unconnected-(U1-A12-Pad4)") (class "Default")
      (node (ref "U1") (pin "4") (pinfunction "A12_4") (pintype "input"))
    )
    (net (code "156") (name "unconnected-(U1-A13-Pad28)") (class "Default")
      (node (ref "U1") (pin "28") (pinfunction "A13_28") (pintype "input"))
    )
    (net (code "157") (name "unconnected-(U1-A14-Pad3)") (class "Default")
      (node (ref "U1") (pin "3") (pinfunction "A14_3") (pintype "input"))
    )
    (net (code "158") (name "unconnected-(U1-A15-Pad31)") (class "Default")
      (node (ref "U1") (pin "31") (pinfunction "A15_31") (pintype "input"))
    )
    (net (code "159") (name "unconnected-(U1-A16-Pad2)") (class "Default")
      (node (ref "U1") (pin "2") (pinfunction "A16_2") (pintype "input"))
    )
    (net (code "160") (name "unconnected-(U1-A17-Pad30)") (class "Default")
      (node (ref "U1") (pin "30") (pinfunction "A17_30") (pintype "input"))
    )
    (net (code "161") (name "unconnected-(U1-A18-Pad1)") (class "Default")
      (node (ref "U1") (pin "1") (pinfunction "A18_1") (pintype "no_connect"))
    )
    (net (code "162") (name "unconnected-(U1-CE-Pad22)") (class "Default")
      (node (ref "U1") (pin "22") (pinfunction "CE_22") (pintype "input"))
    )
    (net (code "163") (name "unconnected-(U1-DQ0-Pad13)") (class "Default")
      (node (ref "U1") (pin "13") (pinfunction "DQ0_13") (pintype "bidirectional"))
    )
    (net (code "164") (name "unconnected-(U1-DQ1-Pad14)") (class "Default")
      (node (ref "U1") (pin "14") (pinfunction "DQ1_14") (pintype "bidirectional"))
    )
    (net (code "165") (name "unconnected-(U1-DQ2-Pad15)") (class "Default")
      (node (ref "U1") (pin "15") (pinfunction "DQ2_15") (pintype "bidirectional"))
    )
    (net (code "166") (name "unconnected-(U1-DQ3-Pad17)") (class "Default")
      (node (ref "U1") (pin "17") (pinfunction "DQ3_17") (pintype "bidirectional"))
    )
    (net (code "167") (name "unconnected-(U1-DQ4-Pad18)") (class "Default")
      (node (ref "U1") (pin "18") (pinfunction "DQ4_18") (pintype "bidirectional"))
    )
    (net (code "168") (name "unconnected-(U1-DQ5-Pad19)") (class "Default")
      (node (ref "U1") (pin "19") (pinfunction "DQ5_19") (pintype "bidirectional"))
    )
    (net (code "169") (name "unconnected-(U1-DQ6-Pad20)") (class "Default")
      (node (ref "U1") (pin "20") (pinfunction "DQ6_20") (pintype "bidirectional"))
    )
    (net (code "170") (name "unconnected-(U1-DQ7-Pad21)") (class "Default")
      (node (ref "U1") (pin "21") (pinfunction "DQ7_21") (pintype "bidirectional"))
    )
    (net (code "171") (name "unconnected-(U1-OE-Pad24)") (class "Default")
      (node (ref "U1") (pin "24") (pinfunction "OE_24") (pintype "input"))
    )
    (net (code "172") (name "unconnected-(U1-WE-Pad29)") (class "Default")
      (node (ref "U1") (pin "29") (pinfunction "WE_29") (pintype "input"))
    )
  )
)
